# LP_ECG_Main-X02.net
KiCad netlist of a schematic drawn in Altium Designer
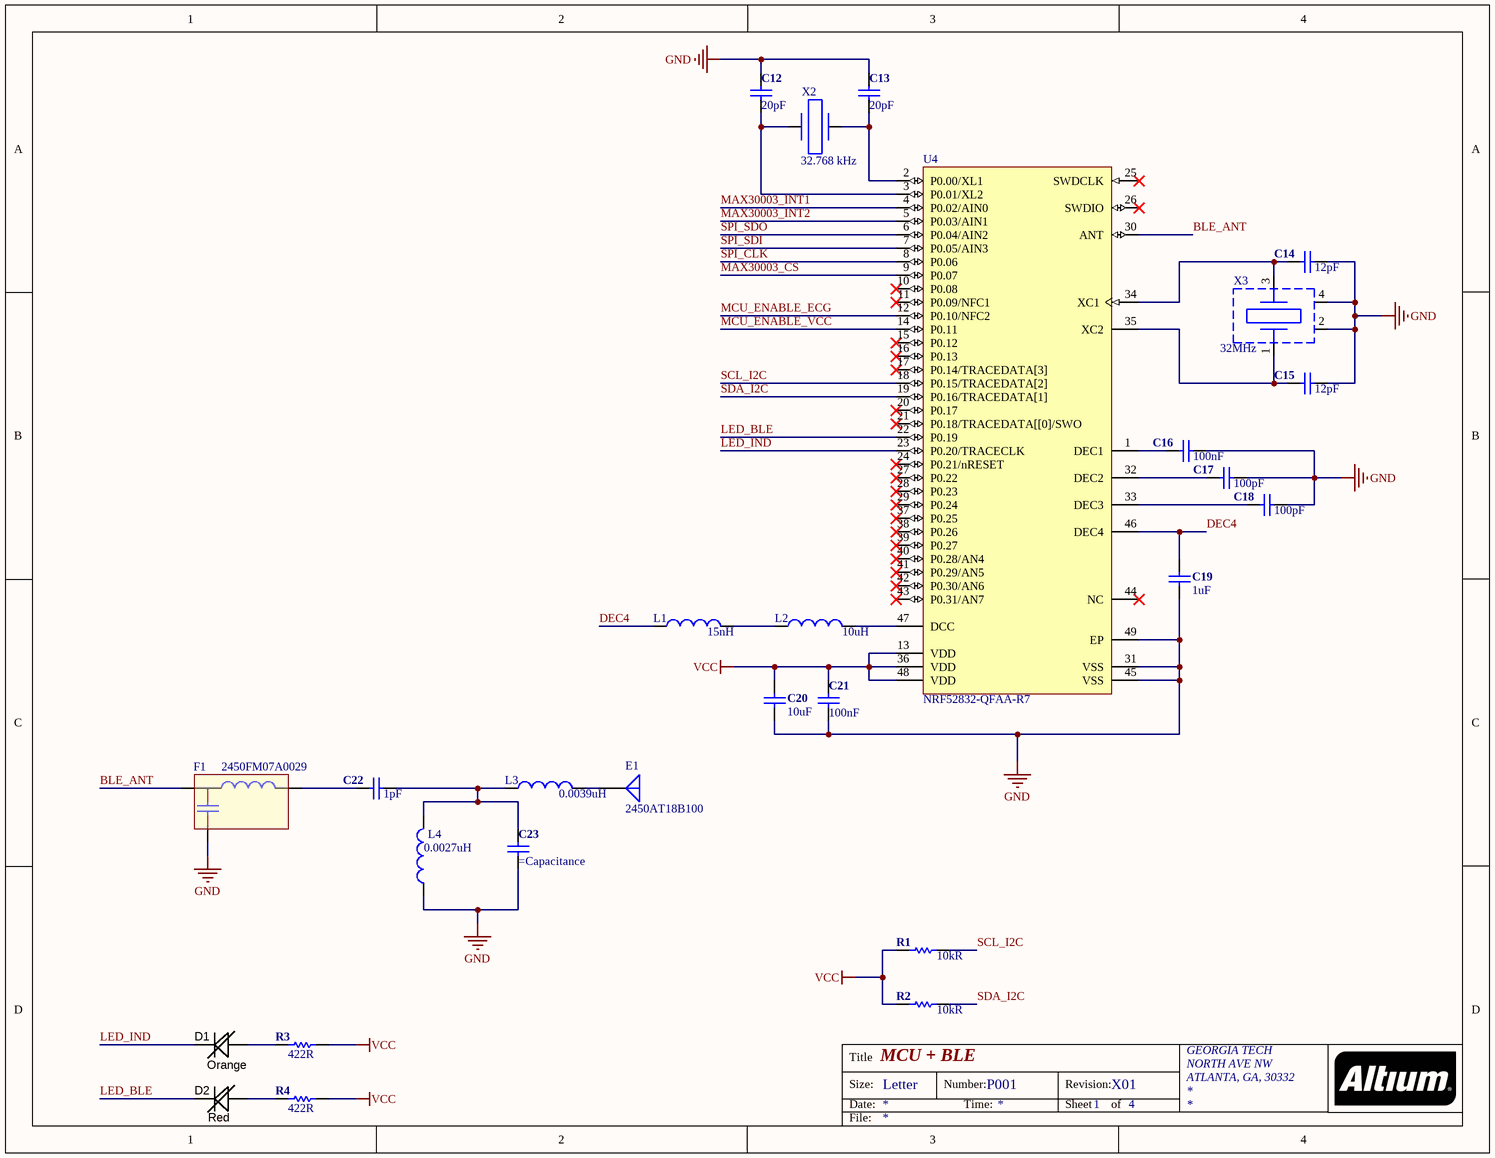
[diagram p0: LP_ECG_Main-X02.SchDoc]

(export (version "E")
  (design (tool "Eeschema 10.0.6"))
  (components
    (comp (ref "C12")
      (value "20pF")
      (footprint "C0402")
      (fields
        (field (name "MANUFACTURER") "Murata")
        (field (name "MANUFACTURER PART NUMBER") "GJM1555C1H200FB01D")
      )
      (libsource (lib "LP_ECG-X01") (part "C-0402(1005)"))
    )
    (comp (ref "C13")
      (value "20pF")
      (footprint "C0402")
      (fields
        (field (name "MANUFACTURER") "Murata")
        (field (name "MANUFACTURER PART NUMBER") "GJM1555C1H200FB01D")
      )
      (libsource (lib "LP_ECG-X01") (part "C-0402(1005)"))
    )
    (comp (ref "C14")
      (value "12pF")
      (footprint "C0402")
      (fields
        (field (name "MANUFACTURER") "Kyocera AVX")
        (field (name "MANUFACTURER PART NUMBER") "04025U120FAT2A")
        (field (name "TOLERANCE") "1%")
      )
      (libsource (lib "LP_ECG-X01") (part "C-0402(1005)"))
    )
    (comp (ref "C15")
      (value "12pF")
      (footprint "C0402")
      (fields
        (field (name "MANUFACTURER") "Kyocera AVX")
        (field (name "MANUFACTURER PART NUMBER") "04025U120FAT2A")
        (field (name "TOLERANCE") "1%")
      )
      (libsource (lib "LP_ECG-X01") (part "C-0402(1005)"))
    )
    (comp (ref "C16")
      (value "100nF")
      (footprint "C0402")
      (fields
        (field (name "MANUFACTURER") "Taiyo Yuden")
        (field (name "MANUFACTURER PART NUMBER") "TMK105BJ104KV-F")
        (field (name "TOLERANCE") "10%")
      )
      (libsource (lib "LP_ECG-X01") (part "C-0402(1005)"))
    )
    (comp (ref "C17")
      (value "100pF")
      (footprint "C0402")
      (fields
        (field (name "MANUFACTURER") "Yageo")
        (field (name "MANUFACTURER PART NUMBER") "CC0402FRNPO9BN101")
        (field (name "TOLERANCE") "1%")
      )
      (libsource (lib "LP_ECG-X01") (part "C-0402(1005)"))
    )
    (comp (ref "C18")
      (value "100pF")
      (footprint "C0402")
      (fields
        (field (name "MANUFACTURER") "Yageo")
        (field (name "MANUFACTURER PART NUMBER") "CC0402FRNPO9BN101")
        (field (name "TOLERANCE") "1%")
      )
      (libsource (lib "LP_ECG-X01") (part "C-0402(1005)"))
    )
    (comp (ref "C19")
      (value "1uF")
      (footprint "C0402")
      (fields
        (field (name "MANUFACTURER") "Yageo")
        (field (name "MANUFACTURER PART NUMBER") "CC0402MRX5R5BB105")
        (field (name "TOLERANCE") "20%")
      )
      (libsource (lib "LP_ECG-X01") (part "C-0402(1005)"))
    )
    (comp (ref "C20")
      (value "10uF")
      (footprint "C0402")
      (fields
        (field (name "MANUFACTURER") "Kyocera AVX")
        (field (name "MANUFACTURER PART NUMBER") "0402ZD106MAT2A")
      )
      (libsource (lib "LP_ECG-X01") (part "C-0402(1005)"))
    )
    (comp (ref "C21")
      (value "100nF")
      (footprint "C0402")
      (fields
        (field (name "MANUFACTURER") "Taiyo Yuden")
        (field (name "MANUFACTURER PART NUMBER") "TMK105BJ104KV-F")
      )
      (libsource (lib "LP_ECG-X01") (part "C-0402(1005)"))
    )
    (comp (ref "C22")
      (value "1pF")
      (footprint "C0402")
      (fields
        (field (name "MANUFACTURER") "Murata")
        (field (name "MANUFACTURER PART NUMBER") "GCQ1555C1H1R0BB01D")
      )
      (libsource (lib "LP_ECG-X01") (part "C-0402(1005)"))
    )
    (comp (ref "C23") (value "~") (footprint "C0402") (libsource (lib "LP_ECG-X01") (part "C-0402(1005)")))
    (comp (ref "D1")
      (value "Orange")
      (footprint "LED_0402")
      (description "Single Color LED, Super Bright Orange, Water Clear, 0.8mm")
      (fields
        (field (name "MANUFACTURER") "Kingbright")
        (field (name "MANUFACTURER PART NUMBER") "APHHS1005SECK")
      )
      (libsource (lib "LP_ECG-X01") (part "LED_0402(1005)"))
    )
    (comp (ref "D2")
      (value "Red")
      (footprint "LED_0402")
      (description "Single Color LED, Hyper Red, Water Clear, 0.8mm")
      (fields
        (field (name "MANUFACTURER") "Kingbright")
        (field (name "MANUFACTURER PART NUMBER") "APHHS1005SURCK")
      )
      (libsource (lib "LP_ECG-X01") (part "LED_0402(1005)"))
    )
    (comp (ref "E1")
      (value "2450AT18B100")
      (footprint "2450AT18B100")
      (description "RF/Microwave Antenna, 2400MHz Min, 2500MHz Max")
      (fields
        (field (name "MANUFACTURER") "Johanson")
        (field (name "MANUFACTURER PART NUMBER") "2450AT18B100E")
      )
      (libsource (lib "LP_ECG-X01") (part "2450AT18B100"))
    )
    (comp (ref "F1")
      (value "2450FM07A0029")
      (footprint "2450FM07A0029")
      (description "Ceramic LPF")
      (fields
        (field (name "MANUFACTURER") "Johanson")
        (field (name "MANUFACTURER PART NUMBER") "2450FM07A0029T")
      )
      (libsource (lib "LP_ECG-X02") (part "2450FM07A0029"))
    )
    (comp (ref "L1")
      (value "15nH")
      (footprint "L0402")
      (description "General Purpose Inductor, 0.015uH, 5%, 1 Element, Ferrite-Core, SMD, 0402")
      (fields
        (field (name "MANUFACTURER") "Taiyo Yuden")
        (field (name "MANUFACTURER PART NUMBER") "HK100515NJ-T")
      )
      (libsource (lib "LP_ECG-X01") (part "I-0402(1005)"))
    )
    (comp (ref "L2")
      (value "10uH")
      (footprint "L0603")
      (description "General Purpose Inductor, 10uH, 10%, 1 Element, Ferrite-Core, SMD, 0603")
      (fields
        (field (name "MANUFACTURER") "Taiyo Yuden")
        (field (name "MANUFACTURER PART NUMBER") "CBMF1608T100K")
      )
      (libsource (lib "LP_ECG-X01") (part "I-0603(1608)"))
    )
    (comp (ref "L3")
      (value "0.0039uH")
      (footprint "L0402")
      (description "General Purpose Inductor, 0.0039uH, 5%, 1 Element, Ceramic-Core, SMD, 0402")
      (fields
        (field (name "MANUFACTURER") "Bourns")
        (field (name "MANUFACTURER PART NUMBER") "CW100505-3N9J")
      )
      (libsource (lib "LP_ECG-X01") (part "I-0402(1005)"))
    )
    (comp (ref "L4")
      (value "0.0027uH")
      (footprint "L0402")
      (description "General Purpose Inductor, 0.0027uH, 2%, 1 Element, SMD, 0402")
      (fields
        (field (name "MANUFACTURER") "Murata")
        (field (name "MANUFACTURER PART NUMBER") "LQW15AN2N7G8ZD")
      )
      (libsource (lib "LP_ECG-X01") (part "I-0402(1005)"))
    )
    (comp (ref "R1")
      (value "10kR")
      (footprint "R0402")
      (fields
        (field (name "MANUFACTURER") "Yageo")
        (field (name "MANUFACTURER PART NUMBER") "AC0402FR-0710KL")
        (field (name "TOLERANCE") "1%")
      )
      (libsource (lib "LP_ECG-X01") (part "R-0402(1005)"))
    )
    (comp (ref "R2")
      (value "10kR")
      (footprint "R0402")
      (fields
        (field (name "MANUFACTURER") "Yageo")
        (field (name "MANUFACTURER PART NUMBER") "AC0402FR-0710KL")
        (field (name "TOLERANCE") "1%")
      )
      (libsource (lib "LP_ECG-X01") (part "R-0402(1005)"))
    )
    (comp (ref "R3")
      (value "422R")
      (footprint "R0402")
      (description "Fixed Resistor, Thin Film, 0.0625W, 422ohm, 50V, 0.1% +/-Tol, 25ppm/Cel, Surface Mount, 0402")
      (fields
        (field (name "MANUFACTURER") "Yageo")
        (field (name "MANUFACTURER PART NUMBER") "RT0402BRD07422RL")
      )
      (libsource (lib "LP_ECG-X01") (part "R-0402(1005)"))
    )
    (comp (ref "R4")
      (value "422R")
      (footprint "R0402")
      (description "Fixed Resistor, Thin Film, 0.0625W, 422ohm, 50V, 0.1% +/-Tol, 25ppm/Cel, Surface Mount, 0402")
      (fields
        (field (name "MANUFACTURER") "Yageo")
        (field (name "MANUFACTURER PART NUMBER") "RT0402BRD07422RL")
      )
      (libsource (lib "LP_ECG-X01") (part "R-0402(1005)"))
    )
    (comp (ref "U4")
      (value "NRF52832-QFAA-R7")
      (footprint "NRF52832-QFAA-R7")
      (description "Telecom Circuit, 1-Func")
      (fields
        (field (name "MANUFACTURER") "Nordic Semiconductor")
        (field (name "MANUFACTURER PART NUMBER") "NRF52832-QFAB-R")
      )
      (libsource (lib "LP_ECG-X01") (part "NRSC-NRF52832-QF-48"))
    )
    (comp (ref "X2")
      (value "32.768 kHz")
      (footprint "CRYSTAL_1MM2_X_1MM0")
      (description "Parallel - Fundamental Quartz Crystal, 0.032768MHz Nom")
      (fields
        (field (name "MANUFACTURER") "ECS International")
        (field (name "MANUFACTURER PART NUMBER") "ECS-.327-12.5-1210-TR")
      )
      (libsource (lib "LP_ECG-X01") (part "CRYSTAL_32K768"))
    )
    (comp (ref "X3")
      (value "32MHz")
      (footprint "CRYSTAL_1MM6_X_1MM2")
      (description "Parallel - Fundamental Quartz Crystal, 32MHz Nom")
      (fields (field (name "MANUFACTURER") "Diodes") (field (name "MANUFACTURER PART NUMBER") "US3200005Z"))
      (libsource (lib "LP_ECG-X01") (part "CRYSTAL_32MHz"))
    )
  )
  (nets
    (net (code "1") (name "/BLE_ANT") (class "Default")
      (node (ref "F1") (pin "1") (pinfunction "1_1") (pintype "passive"))
      (node (ref "U4") (pin "30") (pinfunction "ANT_30") (pintype "bidirectional"))
    )
    (net (code "2") (name "/DEC4") (class "Default")
      (node (ref "C19") (pin "2") (pinfunction "2_2") (pintype "passive"))
      (node (ref "L1") (pin "1") (pinfunction "1_1") (pintype "passive"))
      (node (ref "U4") (pin "46") (pinfunction "DEC4_46") (pintype "passive"))
    )
    (net (code "3") (name "/LED_BLE") (class "Default")
      (node (ref "D2") (pin "K") (pinfunction "K_K") (pintype "passive"))
      (node (ref "U4") (pin "22") (pinfunction "P0.19_22") (pintype "bidirectional"))
    )
    (net (code "4") (name "/LED_IND") (class "Default")
      (node (ref "D1") (pin "K") (pinfunction "K_K") (pintype "passive"))
      (node (ref "U4") (pin "23") (pinfunction "P0.20/TRACECLK_23") (pintype "bidirectional"))
    )
    (net (code "5") (name "/MAX30003_CS") (class "Default")
      (node (ref "U4") (pin "9") (pinfunction "P0.07_9") (pintype "bidirectional"))
    )
    (net (code "6") (name "/MAX30003_INT1") (class "Default")
      (node (ref "U4") (pin "4") (pinfunction "P0.02/AIN0_4") (pintype "bidirectional"))
    )
    (net (code "7") (name "/MAX30003_INT2") (class "Default")
      (node (ref "U4") (pin "5") (pinfunction "P0.03/AIN1_5") (pintype "bidirectional"))
    )
    (net (code "8") (name "/MCU_ENABLE_ECG") (class "Default")
      (node (ref "U4") (pin "12") (pinfunction "P0.10/NFC2_12") (pintype "bidirectional"))
    )
    (net (code "9") (name "/MCU_ENABLE_VCC") (class "Default")
      (node (ref "U4") (pin "14") (pinfunction "P0.11_14") (pintype "bidirectional"))
    )
    (net (code "10") (name "/SCL_I2C") (class "Default")
      (node (ref "R1") (pin "2") (pinfunction "2_2") (pintype "passive"))
      (node (ref "U4") (pin "18") (pinfunction "P0.15/TRACEDATA[2]_18") (pintype "bidirectional"))
    )
    (net (code "11") (name "/SDA_I2C") (class "Default")
      (node (ref "R2") (pin "2") (pinfunction "2_2") (pintype "passive"))
      (node (ref "U4") (pin "19") (pinfunction "P0.16/TRACEDATA[1]_19") (pintype "bidirectional"))
    )
    (net (code "12") (name "/SPI_CLK") (class "Default")
      (node (ref "U4") (pin "8") (pinfunction "P0.06_8") (pintype "bidirectional"))
    )
    (net (code "13") (name "/SPI_SDI") (class "Default")
      (node (ref "U4") (pin "7") (pinfunction "P0.05/AIN3_7") (pintype "bidirectional"))
    )
    (net (code "14") (name "/SPI_SDO") (class "Default")
      (node (ref "U4") (pin "6") (pinfunction "P0.04/AIN2_6") (pintype "bidirectional"))
    )
    (net (code "15") (name "GND") (class "Default")
      (node (ref "C12") (pin "1") (pinfunction "1_1") (pintype "passive"))
      (node (ref "C13") (pin "1") (pinfunction "1_1") (pintype "passive"))
      (node (ref "C14") (pin "2") (pinfunction "2_2") (pintype "passive"))
      (node (ref "C15") (pin "2") (pinfunction "2_2") (pintype "passive"))
      (node (ref "C16") (pin "2") (pinfunction "2_2") (pintype "passive"))
      (node (ref "C17") (pin "2") (pinfunction "2_2") (pintype "passive"))
      (node (ref "C18") (pin "2") (pinfunction "2_2") (pintype "passive"))
      (node (ref "C19") (pin "1") (pinfunction "1_1") (pintype "passive"))
      (node (ref "C20") (pin "2") (pinfunction "2_2") (pintype "passive"))
      (node (ref "C21") (pin "2") (pinfunction "2_2") (pintype "passive"))
      (node (ref "C23") (pin "2") (pinfunction "2_2") (pintype "passive"))
      (node (ref "F1") (pin "3") (pinfunction "3_3") (pintype "passive"))
      (node (ref "L4") (pin "1") (pinfunction "1_1") (pintype "passive"))
      (node (ref "U4") (pin "31") (pinfunction "VSS_31") (pintype "power_in"))
      (node (ref "U4") (pin "45") (pinfunction "VSS_45") (pintype "power_in"))
      (node (ref "U4") (pin "49") (pinfunction "EP_49") (pintype "power_in"))
      (node (ref "X3") (pin "2") (pinfunction "GND_2") (pintype "passive"))
      (node (ref "X3") (pin "4") (pinfunction "GND_4") (pintype "passive"))
    )
    (net (code "16") (name "Net-(C22-Pad1)") (class "Default")
      (node (ref "C22") (pin "1") (pinfunction "1_1") (pintype "passive"))
      (node (ref "F1") (pin "2") (pinfunction "2_2") (pintype "passive"))
    )
    (net (code "17") (name "Net-(C22-Pad2)") (class "Default")
      (node (ref "C22") (pin "2") (pinfunction "2_2") (pintype "passive"))
      (node (ref "C23") (pin "1") (pinfunction "1_1") (pintype "passive"))
      (node (ref "L3") (pin "1") (pinfunction "1_1") (pintype "passive"))
      (node (ref "L4") (pin "2") (pinfunction "2_2") (pintype "passive"))
    )
    (net (code "18") (name "Net-(D1-PadA)") (class "Default")
      (node (ref "D1") (pin "A") (pinfunction "A_A") (pintype "passive"))
      (node (ref "R3") (pin "2") (pinfunction "2_2") (pintype "passive"))
    )
    (net (code "19") (name "Net-(D2-PadA)") (class "Default")
      (node (ref "D2") (pin "A") (pinfunction "A_A") (pintype "passive"))
      (node (ref "R4") (pin "2") (pinfunction "2_2") (pintype "passive"))
    )
    (net (code "20") (name "Net-(E1-A)") (class "Default")
      (node (ref "E1") (pin "1") (pinfunction "A_1") (pintype "passive"))
      (node (ref "L3") (pin "2") (pinfunction "2_2") (pintype "passive"))
    )
    (net (code "21") (name "Net-(L1-Pad2)") (class "Default")
      (node (ref "L1") (pin "2") (pinfunction "2_2") (pintype "passive"))
      (node (ref "L2") (pin "1") (pinfunction "1_1") (pintype "passive"))
    )
    (net (code "22") (name "Net-(U4-DCC)") (class "Default")
      (node (ref "L2") (pin "2") (pinfunction "2_2") (pintype "passive"))
      (node (ref "U4") (pin "47") (pinfunction "DCC_47") (pintype "power_in"))
    )
    (net (code "23") (name "Net-(U4-DEC1)") (class "Default")
      (node (ref "C16") (pin "1") (pinfunction "1_1") (pintype "passive"))
      (node (ref "U4") (pin "1") (pinfunction "DEC1_1") (pintype "passive"))
    )
    (net (code "24") (name "Net-(U4-DEC2)") (class "Default")
      (node (ref "C17") (pin "1") (pinfunction "1_1") (pintype "passive"))
      (node (ref "U4") (pin "32") (pinfunction "DEC2_32") (pintype "passive"))
    )
    (net (code "25") (name "Net-(U4-DEC3)") (class "Default")
      (node (ref "C18") (pin "1") (pinfunction "1_1") (pintype "passive"))
      (node (ref "U4") (pin "33") (pinfunction "DEC3_33") (pintype "passive"))
    )
    (net (code "26") (name "Net-(U4-P0.00{slash}XL1)") (class "Default")
      (node (ref "C13") (pin "2") (pinfunction "2_2") (pintype "passive"))
      (node (ref "U4") (pin "2") (pinfunction "P0.00/XL1_2") (pintype "bidirectional"))
      (node (ref "X2") (pin "2") (pinfunction "2_2") (pintype "passive"))
    )
    (net (code "27") (name "Net-(U4-P0.01{slash}XL2)") (class "Default")
      (node (ref "C12") (pin "2") (pinfunction "2_2") (pintype "passive"))
      (node (ref "U4") (pin "3") (pinfunction "P0.01/XL2_3") (pintype "bidirectional"))
      (node (ref "X2") (pin "1") (pinfunction "1_1") (pintype "passive"))
    )
    (net (code "28") (name "Net-(U4-XC1)") (class "Default")
      (node (ref "C14") (pin "1") (pinfunction "1_1") (pintype "passive"))
      (node (ref "U4") (pin "34") (pinfunction "XC1_34") (pintype "input"))
      (node (ref "X3") (pin "3") (pinfunction "3_3") (pintype "passive"))
    )
    (net (code "29") (name "Net-(U4-XC2)") (class "Default")
      (node (ref "C15") (pin "1") (pinfunction "1_1") (pintype "passive"))
      (node (ref "U4") (pin "35") (pinfunction "XC2_35") (pintype "passive"))
      (node (ref "X3") (pin "1") (pinfunction "1_1") (pintype "passive"))
    )
    (net (code "30") (name "VCC") (class "Default")
      (node (ref "C20") (pin "1") (pinfunction "1_1") (pintype "passive"))
      (node (ref "C21") (pin "1") (pinfunction "1_1") (pintype "passive"))
      (node (ref "R1") (pin "1") (pinfunction "1_1") (pintype "passive"))
      (node (ref "R2") (pin "1") (pinfunction "1_1") (pintype "passive"))
      (node (ref "R3") (pin "1") (pinfunction "1_1") (pintype "passive"))
      (node (ref "R4") (pin "1") (pinfunction "1_1") (pintype "passive"))
      (node (ref "U4") (pin "13") (pinfunction "VDD_13") (pintype "power_in"))
      (node (ref "U4") (pin "36") (pinfunction "VDD_36") (pintype "power_in"))
      (node (ref "U4") (pin "48") (pinfunction "VDD_48") (pintype "power_in"))
    )
    (net (code "31") (name "unconnected-(U4-NC-Pad44)") (class "Default")
      (node (ref "U4") (pin "44") (pinfunction "NC_44") (pintype "passive+no_connect"))
    )
    (net (code "32") (name "unconnected-(U4-P0.08-Pad10)") (class "Default")
      (node (ref "U4") (pin "10") (pinfunction "P0.08_10") (pintype "bidirectional+no_connect"))
    )
    (net (code "33") (name "unconnected-(U4-P0.09{slash}NFC1-Pad11)") (class "Default")
      (node (ref "U4") (pin "11") (pinfunction "P0.09/NFC1_11") (pintype "bidirectional+no_connect"))
    )
    (net (code "34") (name "unconnected-(U4-P0.12-Pad15)") (class "Default")
      (node (ref "U4") (pin "15") (pinfunction "P0.12_15") (pintype "bidirectional+no_connect"))
    )
    (net (code "35") (name "unconnected-(U4-P0.13-Pad16)") (class "Default")
      (node (ref "U4") (pin "16") (pinfunction "P0.13_16") (pintype "bidirectional+no_connect"))
    )
    (net (code "36") (name "unconnected-(U4-P0.14{slash}TRACEDATA[3]-Pad17)") (class "Default")
      (node (ref "U4") (pin "17") (pinfunction "P0.14/TRACEDATA[3]_17") (pintype "bidirectional+no_connect"))
    )
    (net (code "37") (name "unconnected-(U4-P0.17-Pad20)") (class "Default")
      (node (ref "U4") (pin "20") (pinfunction "P0.17_20") (pintype "bidirectional+no_connect"))
    )
    (net (code "38") (name "unconnected-(U4-P0.18{slash}TRACEDATA[[0]{slash}SWO-Pad21)") (class "Default")
      (node (ref "U4") (pin "21") (pinfunction "P0.18/TRACEDATA[[0]/SWO_21") (pintype "bidirectional+no_connect"))
    )
    (net (code "39") (name "unconnected-(U4-P0.21{slash}nRESET-Pad24)") (class "Default")
      (node (ref "U4") (pin "24") (pinfunction "P0.21/nRESET_24") (pintype "bidirectional+no_connect"))
    )
    (net (code "40") (name "unconnected-(U4-P0.22-Pad27)") (class "Default")
      (node (ref "U4") (pin "27") (pinfunction "P0.22_27") (pintype "bidirectional+no_connect"))
    )
    (net (code "41") (name "unconnected-(U4-P0.23-Pad28)") (class "Default")
      (node (ref "U4") (pin "28") (pinfunction "P0.23_28") (pintype "bidirectional+no_connect"))
    )
    (net (code "42") (name "unconnected-(U4-P0.24-Pad29)") (class "Default")
      (node (ref "U4") (pin "29") (pinfunction "P0.24_29") (pintype "bidirectional+no_connect"))
    )
    (net (code "43") (name "unconnected-(U4-P0.25-Pad37)") (class "Default")
      (node (ref "U4") (pin "37") (pinfunction "P0.25_37") (pintype "bidirectional+no_connect"))
    )
    (net (code "44") (name "unconnected-(U4-P0.26-Pad38)") (class "Default")
      (node (ref "U4") (pin "38") (pinfunction "P0.26_38") (pintype "bidirectional+no_connect"))
    )
    (net (code "45") (name "unconnected-(U4-P0.27-Pad39)") (class "Default")
      (node (ref "U4") (pin "39") (pinfunction "P0.27_39") (pintype "bidirectional+no_connect"))
    )
    (net (code "46") (name "unconnected-(U4-P0.28{slash}AN4-Pad40)") (class "Default")
      (node (ref "U4") (pin "40") (pinfunction "P0.28/AN4_40") (pintype "bidirectional+no_connect"))
    )
    (net (code "47") (name "unconnected-(U4-P0.29{slash}AN5-Pad41)") (class "Default")
      (node (ref "U4") (pin "41") (pinfunction "P0.29/AN5_41") (pintype "bidirectional+no_connect"))
    )
    (net (code "48") (name "unconnected-(U4-P0.30{slash}AN6-Pad42)") (class "Default")
      (node (ref "U4") (pin "42") (pinfunction "P0.30/AN6_42") (pintype "bidirectional+no_connect"))
    )
    (net (code "49") (name "unconnected-(U4-P0.31{slash}AN7-Pad43)") (class "Default")
      (node (ref "U4") (pin "43") (pinfunction "P0.31/AN7_43") (pintype "bidirectional+no_connect"))
    )
    (net (code "50") (name "unconnected-(U4-SWDCLK-Pad25)") (class "Default")
      (node (ref "U4") (pin "25") (pinfunction "SWDCLK_25") (pintype "input+no_connect"))
    )
    (net (code "51") (name "unconnected-(U4-SWDIO-Pad26)") (class "Default")
      (node (ref "U4") (pin "26") (pinfunction "SWDIO_26") (pintype "bidirectional+no_connect"))
    )
  )
)
